# A-BRIDGE.net
KiCad netlist of a schematic drawn in EAGLE
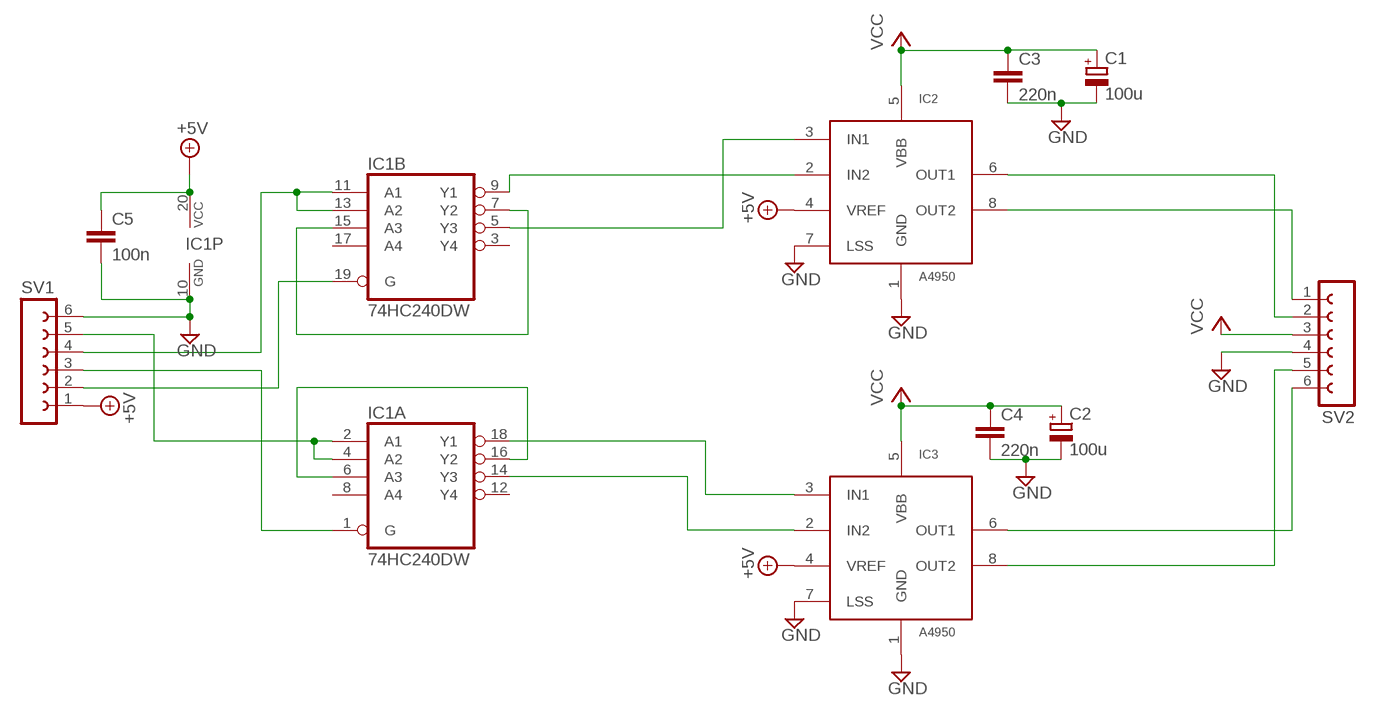
[diagram p0: schematic, sheet 1]

(export (version "E")
  (design (tool "Eeschema 10.0.6"))
  (components
    (comp (ref "C1")
      (value "100u")
      (footprint "eagle-import:UD-6,3X7,7_NICHICON_HS")
      (libsource (lib "eagle-import") (part "CPOL-EUUD-6,3X7,7-HS"))
    )
    (comp (ref "C2")
      (value "100u")
      (footprint "eagle-import:UD-6,3X7,7_NICHICON_HS")
      (libsource (lib "eagle-import") (part "CPOL-EUUD-6,3X7,7-HS"))
    )
    (comp (ref "C3")
      (value "220n")
      (footprint "eagle-import:C0805K")
      (libsource (lib "eagle-import") (part "C-EUC0805K"))
    )
    (comp (ref "C4")
      (value "220n")
      (footprint "eagle-import:C0805K")
      (libsource (lib "eagle-import") (part "C-EUC0805K"))
    )
    (comp (ref "C5")
      (value "100n")
      (footprint "eagle-import:C1206K")
      (libsource (lib "eagle-import") (part "C-EUC1206K"))
    )
    (comp (ref "IC1")
      (value "74HC240DW")
      (footprint "eagle-import:SO20W")
      (libsource (lib "eagle-import") (part "74240DWHC"))
    )
    (comp (ref "IC2")
      (value "A4950")
      (footprint "eagle-import:SOICN-8")
      (libsource (lib "eagle-import") (part "A4950"))
    )
    (comp (ref "IC3")
      (value "A4950")
      (footprint "eagle-import:SOICN-8")
      (libsource (lib "eagle-import") (part "A4950"))
    )
    (comp (ref "SV1")
      (value "FE06-1")
      (footprint "eagle-import:FE06")
      (libsource (lib "eagle-import") (part "FE06-1"))
    )
    (comp (ref "SV2")
      (value "FE06-1")
      (footprint "eagle-import:FE06")
      (libsource (lib "eagle-import") (part "FE06-1"))
    )
  )
  (nets
    (net (code "1") (name "+5V") (class "Default")
      (node (ref "C5") (pin "1") (pinfunction "1_1") (pintype "passive"))
      (node (ref "IC1") (pin "20") (pinfunction "VCC_20") (pintype "power_in"))
      (node (ref "IC2") (pin "4") (pinfunction "VREF_4") (pintype "bidirectional"))
      (node (ref "IC3") (pin "4") (pinfunction "VREF_4") (pintype "bidirectional"))
      (node (ref "SV1") (pin "1") (pinfunction "1_1") (pintype "passive"))
    )
    (net (code "2") (name "GND") (class "Default")
      (node (ref "C1") (pin "-") (pinfunction "-_-") (pintype "passive"))
      (node (ref "C2") (pin "-") (pinfunction "-_-") (pintype "passive"))
      (node (ref "C3") (pin "2") (pinfunction "2_2") (pintype "passive"))
      (node (ref "C4") (pin "2") (pinfunction "2_2") (pintype "passive"))
      (node (ref "C5") (pin "2") (pinfunction "2_2") (pintype "passive"))
      (node (ref "IC1") (pin "10") (pinfunction "GND_10") (pintype "power_in"))
      (node (ref "IC2") (pin "1") (pinfunction "GND_1") (pintype "bidirectional"))
      (node (ref "IC2") (pin "7") (pinfunction "LSS_7") (pintype "bidirectional"))
      (node (ref "IC3") (pin "1") (pinfunction "GND_1") (pintype "bidirectional"))
      (node (ref "IC3") (pin "7") (pinfunction "LSS_7") (pintype "bidirectional"))
      (node (ref "SV1") (pin "6") (pinfunction "6_6") (pintype "passive"))
      (node (ref "SV2") (pin "4") (pinfunction "4_4") (pintype "passive"))
    )
    (net (code "3") (name "Net-(IC1A-A1)") (class "Default")
      (node (ref "IC1") (pin "2") (pinfunction "A1_2") (pintype "input"))
      (node (ref "IC1") (pin "4") (pinfunction "A2_4") (pintype "input"))
      (node (ref "SV1") (pin "5") (pinfunction "5_5") (pintype "passive"))
    )
    (net (code "4") (name "Net-(IC1A-A3)") (class "Default")
      (node (ref "IC1") (pin "16") (pinfunction "Y2_16") (pintype "tri_state"))
      (node (ref "IC1") (pin "6") (pinfunction "A3_6") (pintype "input"))
    )
    (net (code "5") (name "Net-(IC1A-G)") (class "Default")
      (node (ref "IC1") (pin "1") (pinfunction "G_1") (pintype "input"))
      (node (ref "SV1") (pin "3") (pinfunction "3_3") (pintype "passive"))
    )
    (net (code "6") (name "Net-(IC1A-Y1)") (class "Default")
      (node (ref "IC1") (pin "18") (pinfunction "Y1_18") (pintype "tri_state"))
      (node (ref "IC3") (pin "3") (pinfunction "IN1_3") (pintype "bidirectional"))
    )
    (net (code "7") (name "Net-(IC1A-Y3)") (class "Default")
      (node (ref "IC1") (pin "14") (pinfunction "Y3_14") (pintype "tri_state"))
      (node (ref "IC3") (pin "2") (pinfunction "IN2_2") (pintype "bidirectional"))
    )
    (net (code "8") (name "Net-(IC1B-A1)") (class "Default")
      (node (ref "IC1") (pin "11") (pinfunction "A1_11") (pintype "input"))
      (node (ref "IC1") (pin "13") (pinfunction "A2_13") (pintype "input"))
      (node (ref "SV1") (pin "4") (pinfunction "4_4") (pintype "passive"))
    )
    (net (code "9") (name "Net-(IC1B-A3)") (class "Default")
      (node (ref "IC1") (pin "15") (pinfunction "A3_15") (pintype "input"))
      (node (ref "IC1") (pin "7") (pinfunction "Y2_7") (pintype "tri_state"))
    )
    (net (code "10") (name "Net-(IC1B-G)") (class "Default")
      (node (ref "IC1") (pin "19") (pinfunction "G_19") (pintype "input"))
      (node (ref "SV1") (pin "2") (pinfunction "2_2") (pintype "passive"))
    )
    (net (code "11") (name "Net-(IC1B-Y1)") (class "Default")
      (node (ref "IC1") (pin "9") (pinfunction "Y1_9") (pintype "tri_state"))
      (node (ref "IC2") (pin "2") (pinfunction "IN2_2") (pintype "bidirectional"))
    )
    (net (code "12") (name "Net-(IC1B-Y3)") (class "Default")
      (node (ref "IC1") (pin "5") (pinfunction "Y3_5") (pintype "tri_state"))
      (node (ref "IC2") (pin "3") (pinfunction "IN1_3") (pintype "bidirectional"))
    )
    (net (code "13") (name "Net-(IC2-OUT1)") (class "Default")
      (node (ref "IC2") (pin "6") (pinfunction "OUT1_6") (pintype "bidirectional"))
      (node (ref "SV2") (pin "2") (pinfunction "2_2") (pintype "passive"))
    )
    (net (code "14") (name "Net-(IC2-OUT2)") (class "Default")
      (node (ref "IC2") (pin "8") (pinfunction "OUT2_8") (pintype "bidirectional"))
      (node (ref "SV2") (pin "1") (pinfunction "1_1") (pintype "passive"))
    )
    (net (code "15") (name "Net-(IC3-OUT1)") (class "Default")
      (node (ref "IC3") (pin "6") (pinfunction "OUT1_6") (pintype "bidirectional"))
      (node (ref "SV2") (pin "6") (pinfunction "6_6") (pintype "passive"))
    )
    (net (code "16") (name "Net-(IC3-OUT2)") (class "Default")
      (node (ref "IC3") (pin "8") (pinfunction "OUT2_8") (pintype "bidirectional"))
      (node (ref "SV2") (pin "5") (pinfunction "5_5") (pintype "passive"))
    )
    (net (code "17") (name "VCC") (class "Default")
      (node (ref "C1") (pin "+") (pinfunction "+_+") (pintype "passive"))
      (node (ref "C2") (pin "+") (pinfunction "+_+") (pintype "passive"))
      (node (ref "C3") (pin "1") (pinfunction "1_1") (pintype "passive"))
      (node (ref "C4") (pin "1") (pinfunction "1_1") (pintype "passive"))
      (node (ref "IC2") (pin "5") (pinfunction "VBB_5") (pintype "bidirectional"))
      (node (ref "IC3") (pin "5") (pinfunction "VBB_5") (pintype "bidirectional"))
      (node (ref "SV2") (pin "3") (pinfunction "3_3") (pintype "passive"))
    )
    (net (code "18") (name "unconnected-(IC1A-A4-Pad8)") (class "Default")
      (node (ref "IC1") (pin "8") (pinfunction "A4_8") (pintype "input"))
    )
    (net (code "19") (name "unconnected-(IC1A-Y4-Pad12)") (class "Default")
      (node (ref "IC1") (pin "12") (pinfunction "Y4_12") (pintype "tri_state"))
    )
    (net (code "20") (name "unconnected-(IC1B-A4-Pad17)") (class "Default")
      (node (ref "IC1") (pin "17") (pinfunction "A4_17") (pintype "input"))
    )
    (net (code "21") (name "unconnected-(IC1B-Y4-Pad3)") (class "Default")
      (node (ref "IC1") (pin "3") (pinfunction "Y4_3") (pintype "tri_state"))
    )
  )
)
